# Control.net
KiCad netlist of a schematic drawn in Altium Designer
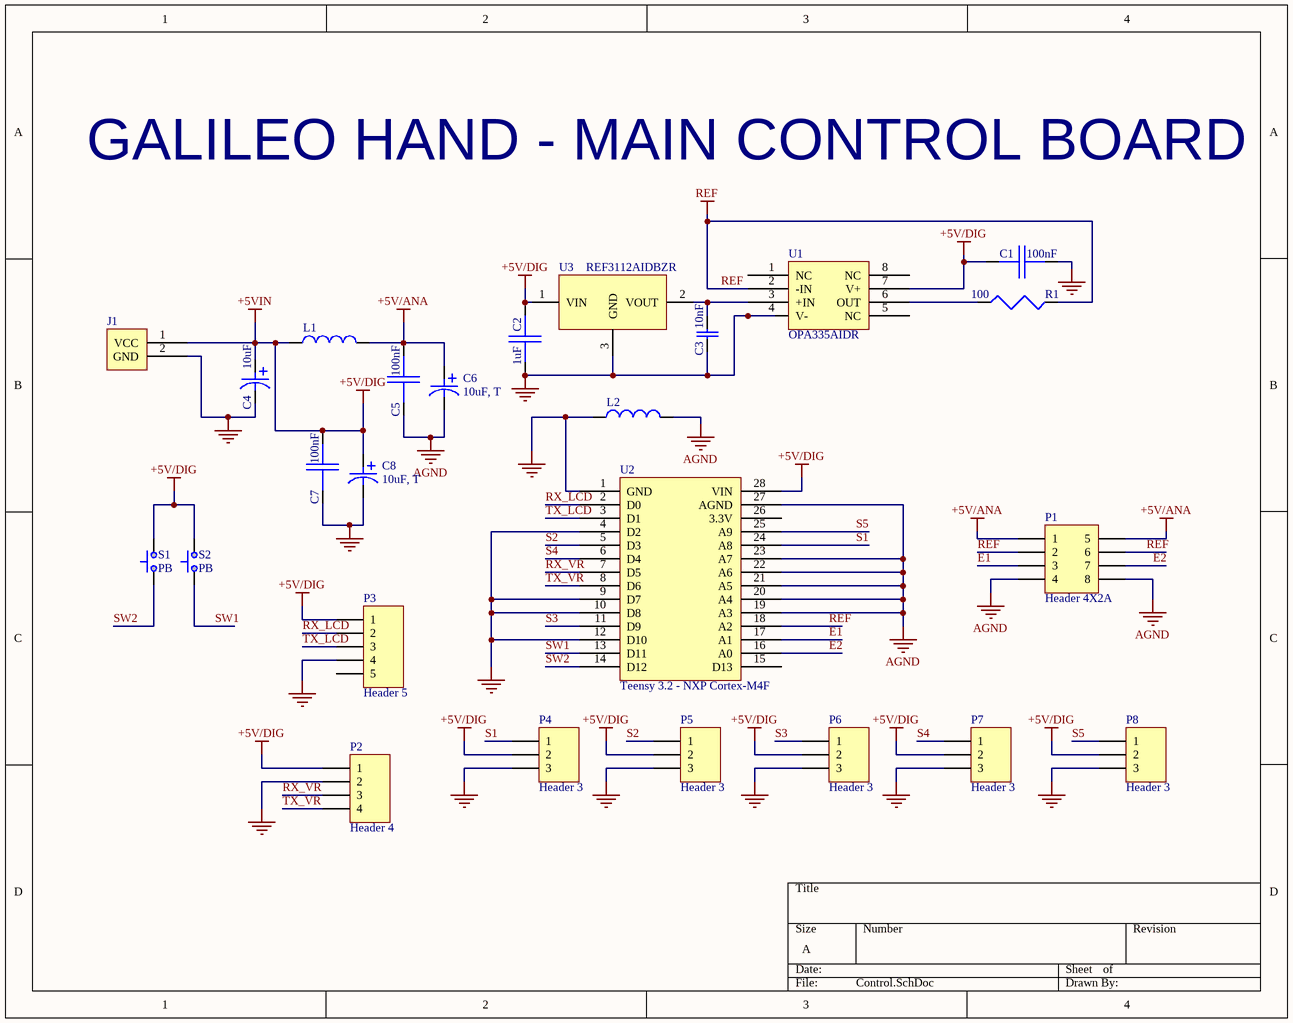
[diagram p0: Control.SchDoc]

(export (version "E")
  (design (tool "Eeschema 10.0.6"))
  (components
    (comp (ref "C1")
      (value "100nF")
      (footprint "C0603")
      (description "CAP CER 0.1UF 25V X7R 0603")
      (fields
        (field (name "MANUFACTURER") "Murata Electronics North America")
        (field (name "MANUFACTURER PART NUMBER") "GRM188R71E104KA01D")
      )
      (libsource (lib "EMG") (part "GRM188R71E104KA01D"))
    )
    (comp (ref "C2")
      (value "1uF")
      (footprint "C0603")
      (description "CAP CER 1UF 25V X5R 0603")
      (fields
        (field (name "MANUFACTURER") "Murata Electronics North America")
        (field (name "MANUFACTURER PART NUMBER") "GRM188R61E105KA12D")
      )
      (libsource (lib "EMG") (part "GRM188R61E105KA12D"))
    )
    (comp (ref "C3")
      (value "10nF")
      (footprint "C0805")
      (description "CAP CER 10000PF 50V X7R 0805")
      (fields
        (field (name "MANUFACTURER") "Murata Electronics North America")
        (field (name "MANUFACTURER PART NUMBER") "GRM216R71H103KA01D")
      )
      (libsource (lib "ISL") (part "GRM216R71H103KA01D"))
    )
    (comp (ref "C4")
      (value "10uF")
      (footprint "CSVB")
      (description "CAP ALUM 10UF 20% 25V SMD")
      (fields
        (field (name "MANUFACTURER") "Panasonic Electronic Components")
        (field (name "MANUFACTURER PART NUMBER") "EEE-1EA100WR")
      )
      (libsource (lib "Control") (part "EEE-1EA100WR"))
    )
    (comp (ref "C5")
      (value "100nF")
      (footprint "C0603")
      (description "CAP CER 0.1UF 25V X7R 0603")
      (fields
        (field (name "MANUFACTURER") "Murata Electronics North America")
        (field (name "MANUFACTURER PART NUMBER") "GRM188R71E104KA01D")
      )
      (libsource (lib "EMG") (part "GRM188R71E104KA01D"))
    )
    (comp (ref "C6")
      (value "10uF, T")
      (footprint "C1206")
      (description "CAP TANT 10UF 20V 10% 2413")
      (fields
        (field (name "MANUFACTURER") "Kemet")
        (field (name "MANUFACTURER PART NUMBER") "T491C106K020AT")
      )
      (libsource (lib "Control") (part "T491C106K020AT"))
    )
    (comp (ref "C7")
      (value "100nF")
      (footprint "C0603")
      (description "CAP CER 0.1UF 25V X7R 0603")
      (fields
        (field (name "MANUFACTURER") "Murata Electronics North America")
        (field (name "MANUFACTURER PART NUMBER") "GRM188R71E104KA01D")
      )
      (libsource (lib "EMG") (part "GRM188R71E104KA01D"))
    )
    (comp (ref "C8")
      (value "10uF, T")
      (footprint "C1206")
      (description "CAP TANT 10UF 20V 10% 2413")
      (fields
        (field (name "MANUFACTURER") "Kemet")
        (field (name "MANUFACTURER PART NUMBER") "T491C106K020AT")
      )
      (libsource (lib "Control") (part "T491C106K020AT"))
    )
    (comp (ref "J1")
      (value "TERMINAL BLOCK  2POS 3.5MM")
      (footprint "2POS3.5mm")
      (description "CONN TERMINAL BLOCK 2POS 3.5MM")
      (fields
        (field (name "MANUFACTURER") "Molex, LLC")
        (field (name "MANUFACTURER PART NUMBER") "0393570002")
      )
      (libsource (lib "Control") (part "0393570002"))
    )
    (comp (ref "L1")
      (value "EMI FILTER BED")
      (footprint "R0603")
      (description "FERRITE BEAD 470 OHM 0603")
      (fields
        (field (name "MANUFACTURER") "Murata Electronics North America")
        (field (name "MANUFACTURER PART NUMBER") "BLM18PG471SN1D")
      )
      (libsource (lib "Control") (part "BLM18PG471SN1D"))
    )
    (comp (ref "L2")
      (value "EMI FILTER BED")
      (footprint "R0603")
      (description "FERRITE BEAD 470 OHM 0603")
      (fields
        (field (name "MANUFACTURER") "Murata Electronics North America")
        (field (name "MANUFACTURER PART NUMBER") "BLM18PG471SN1D")
      )
      (libsource (lib "Control") (part "BLM18PG471SN1D"))
    )
    (comp (ref "P1")
      (value "Header 4X2A")
      (footprint "HDR2X4_CEN")
      (description "Header, 4-Pin, Dual row")
      (fields (field (name "PUBLISHER") "Altium Limited"))
      (libsource (lib "Miscellaneous Connectors") (part "Header 4X2A"))
    )
    (comp (ref "P2")
      (value "Header 4")
      (footprint "HDR1X4")
      (description "Header, 4-Pin")
      (fields (field (name "PUBLISHER") "Altium Limited"))
      (libsource (lib "Miscellaneous Connectors") (part "Header 4"))
    )
    (comp (ref "P3")
      (value "Header 5")
      (footprint "HDR1X5")
      (description "Header, 5-Pin")
      (fields (field (name "PUBLISHER") "Altium Limited"))
      (libsource (lib "Miscellaneous Connectors") (part "Header 5"))
    )
    (comp (ref "P4")
      (value "Header 3")
      (footprint "HDR1X3")
      (description "Header, 3-Pin")
      (fields (field (name "PUBLISHER") "Altium Limited"))
      (libsource (lib "Miscellaneous Connectors") (part "Header 3"))
    )
    (comp (ref "P5")
      (value "Header 3")
      (footprint "HDR1X3")
      (description "Header, 3-Pin")
      (fields (field (name "PUBLISHER") "Altium Limited"))
      (libsource (lib "Miscellaneous Connectors") (part "Header 3"))
    )
    (comp (ref "P6")
      (value "Header 3")
      (footprint "HDR1X3")
      (description "Header, 3-Pin")
      (fields (field (name "PUBLISHER") "Altium Limited"))
      (libsource (lib "Miscellaneous Connectors") (part "Header 3"))
    )
    (comp (ref "P7")
      (value "Header 3")
      (footprint "HDR1X3")
      (description "Header, 3-Pin")
      (fields (field (name "PUBLISHER") "Altium Limited"))
      (libsource (lib "Miscellaneous Connectors") (part "Header 3"))
    )
    (comp (ref "P8")
      (value "Header 3")
      (footprint "HDR1X3")
      (description "Header, 3-Pin")
      (fields (field (name "PUBLISHER") "Altium Limited"))
      (libsource (lib "Miscellaneous Connectors") (part "Header 3"))
    )
    (comp (ref "R1")
      (value "100")
      (footprint "R0603")
      (description "RES SMD 100 OHM 1% 1/10W 0603")
      (fields
        (field (name "MANUFACTURER") "Panasonic Electronic Components")
        (field (name "MANUFACTURER PART NUMBER") "ERJ-3EKF1000V")
      )
      (libsource (lib "EMG") (part "ERJ-3EKF1000V"))
    )
    (comp (ref "S1")
      (value "PB")
      (footprint "SW")
      (description "SWITCH PUSH SPST-NO 0.1A 32V")
      (fields
        (field (name "MANUFACTURER") "C&K Components")
        (field (name "MANUFACTURER PART NUMBER") "D6C90 F1 LFS")
      )
      (libsource (lib "Control") (part "D6C90 F1 LFS"))
    )
    (comp (ref "S2")
      (value "PB")
      (footprint "SW")
      (description "SWITCH PUSH SPST-NO 0.1A 32V")
      (fields
        (field (name "MANUFACTURER") "C&K Components")
        (field (name "MANUFACTURER PART NUMBER") "D6C90 F1 LFS")
      )
      (libsource (lib "Control") (part "D6C90 F1 LFS"))
    )
    (comp (ref "U1")
      (value "OPA335AIDR")
      (footprint "SO-8")
      (description "IC OPAMP CHOPPER 2MHZ RRO 8SOIC")
      (fields (field (name "MANUFACTURER") "Texas Instruments"))
      (libsource (lib "DCDC") (part "OPA335AIDR"))
    )
    (comp (ref "U2")
      (value "Teensy 3.2 - NXP Cortex-M4F")
      (footprint "DIP28")
      (fields
        (field (name "MANUFACTURER") "SparkFun Electronics")
        (field (name "MANUFACTURER PART NUMBER") "DEV-13305")
      )
      (libsource (lib "Control") (part "Teensy"))
    )
    (comp (ref "U3")
      (value "REF3112AIDBZR")
      (footprint "SOT-23")
      (description "IC VREF SERIES 1.25V SOT23-3")
      (fields (field (name "MANUFACTURER") "Texas Instruments") (field (name "TOLERANCE") "±0.2%"))
      (libsource (lib "DCDC") (part "REF3112AIDBZR"))
    )
  )
  (nets
    (net (code "1") (name "+5VIN") (class "Default")
      (node (ref "C1") (pin "2") (pinfunction "2_2") (pintype "passive"))
      (node (ref "C2") (pin "2") (pinfunction "2_2") (pintype "passive"))
      (node (ref "C4") (pin "1") (pinfunction "1_1") (pintype "passive"))
      (node (ref "C7") (pin "2") (pinfunction "2_2") (pintype "passive"))
      (node (ref "C8") (pin "1") (pinfunction "1_1") (pintype "passive"))
      (node (ref "J1") (pin "1") (pinfunction "VCC_1") (pintype "passive"))
      (node (ref "L1") (pin "1") (pinfunction "1_1") (pintype "passive"))
      (node (ref "P2") (pin "1") (pinfunction "1_1") (pintype "passive"))
      (node (ref "P3") (pin "1") (pinfunction "1_1") (pintype "passive"))
      (node (ref "P4") (pin "2") (pinfunction "2_2") (pintype "passive"))
      (node (ref "P5") (pin "2") (pinfunction "2_2") (pintype "passive"))
      (node (ref "P6") (pin "2") (pinfunction "2_2") (pintype "passive"))
      (node (ref "P7") (pin "2") (pinfunction "2_2") (pintype "passive"))
      (node (ref "P8") (pin "2") (pinfunction "2_2") (pintype "passive"))
      (node (ref "S1") (pin "2") (pinfunction "2_2") (pintype "passive"))
      (node (ref "S2") (pin "2") (pinfunction "2_2") (pintype "passive"))
      (node (ref "U1") (pin "7") (pinfunction "V+_7") (pintype "passive"))
      (node (ref "U2") (pin "28") (pinfunction "VIN_28") (pintype "passive"))
      (node (ref "U3") (pin "1") (pinfunction "VIN_1") (pintype "passive"))
    )
    (net (code "2") (name "+5V{slash}ANA") (class "Default")
      (node (ref "C5") (pin "2") (pinfunction "2_2") (pintype "passive"))
      (node (ref "C6") (pin "1") (pinfunction "1_1") (pintype "passive"))
      (node (ref "L1") (pin "2") (pinfunction "2_2") (pintype "passive"))
      (node (ref "P1") (pin "1") (pinfunction "1_1") (pintype "passive"))
      (node (ref "P1") (pin "5") (pinfunction "5_5") (pintype "passive"))
    )
    (net (code "3") (name "/E1") (class "Default")
      (node (ref "P1") (pin "3") (pinfunction "3_3") (pintype "passive"))
      (node (ref "U2") (pin "17") (pinfunction "A1_17") (pintype "passive"))
    )
    (net (code "4") (name "/E2") (class "Default")
      (node (ref "P1") (pin "7") (pinfunction "7_7") (pintype "passive"))
      (node (ref "U2") (pin "16") (pinfunction "A0_16") (pintype "passive"))
    )
    (net (code "5") (name "/RX_LCD") (class "Default")
      (node (ref "P3") (pin "2") (pinfunction "2_2") (pintype "passive"))
      (node (ref "U2") (pin "2") (pinfunction "D0_2") (pintype "passive"))
    )
    (net (code "6") (name "/RX_VR") (class "Default")
      (node (ref "P2") (pin "3") (pinfunction "3_3") (pintype "passive"))
      (node (ref "U2") (pin "7") (pinfunction "D5_7") (pintype "passive"))
    )
    (net (code "7") (name "/S1") (class "Default")
      (node (ref "P4") (pin "1") (pinfunction "1_1") (pintype "passive"))
      (node (ref "U2") (pin "24") (pinfunction "A8_24") (pintype "passive"))
    )
    (net (code "8") (name "/S2") (class "Default")
      (node (ref "P5") (pin "1") (pinfunction "1_1") (pintype "passive"))
      (node (ref "U2") (pin "5") (pinfunction "D3_5") (pintype "passive"))
    )
    (net (code "9") (name "/S3") (class "Default")
      (node (ref "P6") (pin "1") (pinfunction "1_1") (pintype "passive"))
      (node (ref "U2") (pin "11") (pinfunction "D9_11") (pintype "passive"))
    )
    (net (code "10") (name "/S4") (class "Default")
      (node (ref "P7") (pin "1") (pinfunction "1_1") (pintype "passive"))
      (node (ref "U2") (pin "6") (pinfunction "D4_6") (pintype "passive"))
    )
    (net (code "11") (name "/S5") (class "Default")
      (node (ref "P8") (pin "1") (pinfunction "1_1") (pintype "passive"))
      (node (ref "U2") (pin "25") (pinfunction "A9_25") (pintype "passive"))
    )
    (net (code "12") (name "/SW1") (class "Default")
      (node (ref "S2") (pin "1") (pinfunction "1_1") (pintype "passive"))
      (node (ref "U2") (pin "13") (pinfunction "D11_13") (pintype "passive"))
    )
    (net (code "13") (name "/SW2") (class "Default")
      (node (ref "S1") (pin "1") (pinfunction "1_1") (pintype "passive"))
      (node (ref "U2") (pin "14") (pinfunction "D12_14") (pintype "passive"))
    )
    (net (code "14") (name "/TX_LCD") (class "Default")
      (node (ref "P3") (pin "3") (pinfunction "3_3") (pintype "passive"))
      (node (ref "U2") (pin "3") (pinfunction "D1_3") (pintype "passive"))
    )
    (net (code "15") (name "/TX_VR") (class "Default")
      (node (ref "P2") (pin "4") (pinfunction "4_4") (pintype "passive"))
      (node (ref "U2") (pin "8") (pinfunction "D6_8") (pintype "passive"))
    )
    (net (code "16") (name "AGND") (class "Default")
      (node (ref "C5") (pin "1") (pinfunction "1_1") (pintype "passive"))
      (node (ref "C6") (pin "2") (pinfunction "2_2") (pintype "passive"))
      (node (ref "L2") (pin "2") (pinfunction "2_2") (pintype "passive"))
      (node (ref "P1") (pin "4") (pinfunction "4_4") (pintype "passive"))
      (node (ref "P1") (pin "8") (pinfunction "8_8") (pintype "passive"))
      (node (ref "U2") (pin "19") (pinfunction "A3_19") (pintype "passive"))
      (node (ref "U2") (pin "20") (pinfunction "A4_20") (pintype "passive"))
      (node (ref "U2") (pin "21") (pinfunction "A5_21") (pintype "passive"))
      (node (ref "U2") (pin "22") (pinfunction "A6_22") (pintype "passive"))
      (node (ref "U2") (pin "23") (pinfunction "A7_23") (pintype "passive"))
      (node (ref "U2") (pin "27") (pinfunction "AGND_27") (pintype "passive"))
    )
    (net (code "17") (name "GND") (class "Default")
      (node (ref "C1") (pin "1") (pinfunction "1_1") (pintype "passive"))
      (node (ref "C2") (pin "1") (pinfunction "1_1") (pintype "passive"))
      (node (ref "C3") (pin "1") (pinfunction "1_1") (pintype "passive"))
      (node (ref "C4") (pin "2") (pinfunction "2_2") (pintype "passive"))
      (node (ref "C7") (pin "1") (pinfunction "1_1") (pintype "passive"))
      (node (ref "C8") (pin "2") (pinfunction "2_2") (pintype "passive"))
      (node (ref "J1") (pin "2") (pinfunction "GND_2") (pintype "passive"))
      (node (ref "L2") (pin "1") (pinfunction "1_1") (pintype "passive"))
      (node (ref "P2") (pin "2") (pinfunction "2_2") (pintype "passive"))
      (node (ref "P3") (pin "4") (pinfunction "4_4") (pintype "passive"))
      (node (ref "P4") (pin "3") (pinfunction "3_3") (pintype "passive"))
      (node (ref "P5") (pin "3") (pinfunction "3_3") (pintype "passive"))
      (node (ref "P6") (pin "3") (pinfunction "3_3") (pintype "passive"))
      (node (ref "P7") (pin "3") (pinfunction "3_3") (pintype "passive"))
      (node (ref "P8") (pin "3") (pinfunction "3_3") (pintype "passive"))
      (node (ref "U1") (pin "4") (pinfunction "V-_4") (pintype "passive"))
      (node (ref "U2") (pin "1") (pinfunction "GND_1") (pintype "passive"))
      (node (ref "U2") (pin "10") (pinfunction "D8_10") (pintype "passive"))
      (node (ref "U2") (pin "12") (pinfunction "D10_12") (pintype "passive"))
      (node (ref "U2") (pin "4") (pinfunction "D2_4") (pintype "passive"))
      (node (ref "U2") (pin "9") (pinfunction "D7_9") (pintype "passive"))
      (node (ref "U3") (pin "3") (pinfunction "GND_3") (pintype "passive"))
    )
    (net (code "18") (name "Net-(U1-+IN)") (class "Default")
      (node (ref "C3") (pin "2") (pinfunction "2_2") (pintype "passive"))
      (node (ref "U1") (pin "3") (pinfunction "+IN_3") (pintype "passive"))
      (node (ref "U3") (pin "2") (pinfunction "VOUT_2") (pintype "passive"))
    )
    (net (code "19") (name "Net-(U1-OUT)") (class "Default")
      (node (ref "R1") (pin "2") (pinfunction "2_2") (pintype "passive"))
      (node (ref "U1") (pin "6") (pinfunction "OUT_6") (pintype "passive"))
    )
    (net (code "20") (name "REF") (class "Default")
      (node (ref "P1") (pin "2") (pinfunction "2_2") (pintype "passive"))
      (node (ref "P1") (pin "6") (pinfunction "6_6") (pintype "passive"))
      (node (ref "R1") (pin "1") (pinfunction "1_1") (pintype "passive"))
      (node (ref "U1") (pin "2") (pinfunction "-IN_2") (pintype "passive"))
      (node (ref "U2") (pin "18") (pinfunction "A2_18") (pintype "passive"))
    )
    (net (code "21") (name "unconnected-(P3-Pad5)") (class "Default")
      (node (ref "P3") (pin "5") (pinfunction "5_5") (pintype "passive"))
    )
    (net (code "22") (name "unconnected-(U1-NC-Pad1)") (class "Default")
      (node (ref "U1") (pin "1") (pinfunction "NC_1") (pintype "passive"))
    )
    (net (code "23") (name "unconnected-(U1-NC-Pad5)") (class "Default")
      (node (ref "U1") (pin "5") (pinfunction "NC_5") (pintype "passive"))
    )
    (net (code "24") (name "unconnected-(U1-NC-Pad8)") (class "Default")
      (node (ref "U1") (pin "8") (pinfunction "NC_8") (pintype "passive"))
    )
    (net (code "25") (name "unconnected-(U2-3.3V-Pad26)") (class "Default")
      (node (ref "U2") (pin "26") (pinfunction "3.3V_26") (pintype "passive"))
    )
    (net (code "26") (name "unconnected-(U2-D13-Pad15)") (class "Default")
      (node (ref "U2") (pin "15") (pinfunction "D13_15") (pintype "passive"))
    )
  )
)
